# 9V_Converter_Schematic_3_25_2018.net
KiCad netlist of a schematic drawn in Altium Designer
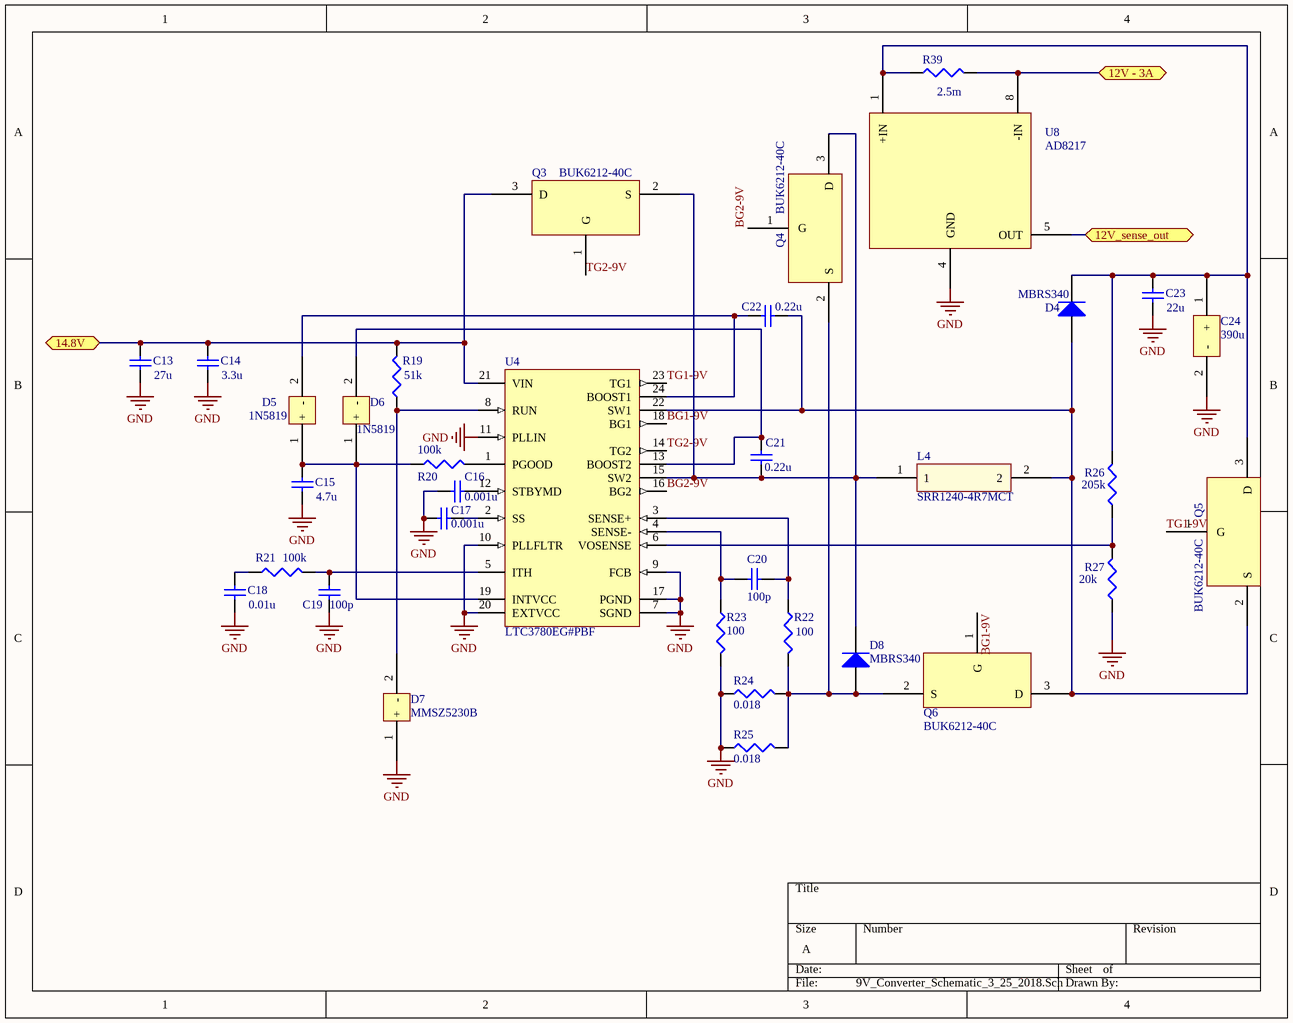
[diagram p0: 9V_Converter_Schematic_3_25_2018.SchDoc]

(export (version "E")
  (design (tool "Eeschema 10.0.6"))
  (components
    (comp (ref "C13")
      (value "27u")
      (footprint "C1206")
      (description "Capacitor (Semiconductor SIM Model)")
      (fields (field (name "Comment") "Cap Semi") (field (name "PUBLISHER") "Altium Limited"))
      (libsource (lib "Miscellaneous Devices") (part "Cap Semi"))
    )
    (comp (ref "C14")
      (value "3.3u")
      (footprint "C1206")
      (description "Capacitor (Semiconductor SIM Model)")
      (fields (field (name "Comment") "Cap Semi") (field (name "PUBLISHER") "Altium Limited"))
      (libsource (lib "Miscellaneous Devices") (part "Cap Semi"))
    )
    (comp (ref "C15")
      (value "4.7u")
      (footprint "C1206")
      (description "Capacitor (Semiconductor SIM Model)")
      (fields (field (name "Comment") "Cap Semi") (field (name "PUBLISHER") "Altium Limited"))
      (libsource (lib "Miscellaneous Devices") (part "Cap Semi"))
    )
    (comp (ref "C16")
      (value "0.001u")
      (footprint "C1206")
      (description "Capacitor (Semiconductor SIM Model)")
      (fields (field (name "Comment") "Cap Semi") (field (name "PUBLISHER") "Altium Limited"))
      (libsource (lib "Miscellaneous Devices") (part "Cap Semi"))
    )
    (comp (ref "C17")
      (value "0.001u")
      (footprint "C1206")
      (description "Capacitor (Semiconductor SIM Model)")
      (fields (field (name "Comment") "Cap Semi") (field (name "PUBLISHER") "Altium Limited"))
      (libsource (lib "Miscellaneous Devices") (part "Cap Semi"))
    )
    (comp (ref "C18")
      (value "0.01u")
      (footprint "C1206")
      (description "Capacitor (Semiconductor SIM Model)")
      (fields (field (name "Comment") "Cap Semi") (field (name "PUBLISHER") "Altium Limited"))
      (libsource (lib "Miscellaneous Devices") (part "Cap Semi"))
    )
    (comp (ref "C19")
      (value "100p")
      (footprint "C1206")
      (description "Capacitor (Semiconductor SIM Model)")
      (fields (field (name "Comment") "Cap Semi") (field (name "PUBLISHER") "Altium Limited"))
      (libsource (lib "Miscellaneous Devices") (part "Cap Semi"))
    )
    (comp (ref "C20")
      (value "100p")
      (footprint "C1206")
      (description "Capacitor (Semiconductor SIM Model)")
      (fields (field (name "Comment") "Cap Semi") (field (name "PUBLISHER") "Altium Limited"))
      (libsource (lib "Miscellaneous Devices") (part "Cap Semi"))
    )
    (comp (ref "C21")
      (value "0.22u")
      (footprint "C1206")
      (description "Capacitor (Semiconductor SIM Model)")
      (fields (field (name "Comment") "Cap Semi") (field (name "PUBLISHER") "Altium Limited"))
      (libsource (lib "Miscellaneous Devices") (part "Cap Semi"))
    )
    (comp (ref "C22")
      (value "0.22u")
      (footprint "C1206")
      (description "Capacitor (Semiconductor SIM Model)")
      (fields (field (name "Comment") "Cap Semi") (field (name "PUBLISHER") "Altium Limited"))
      (libsource (lib "Miscellaneous Devices") (part "Cap Semi"))
    )
    (comp (ref "C23")
      (value "22u")
      (footprint "C1206")
      (description "Capacitor (Semiconductor SIM Model)")
      (fields (field (name "Comment") "Cap Semi") (field (name "PUBLISHER") "Altium Limited"))
      (libsource (lib "Miscellaneous Devices") (part "Cap Semi"))
    )
    (comp (ref "C24") (value "390u") (footprint "Alum_Cap") (libsource (lib "AluminumCap") (part "Alum_Cap")))
    (comp (ref "D4")
      (value "MBRS340")
      (footprint "SMC")
      (description "Default Diode")
      (fields (field (name "PUBLISHER") "Altium Limited"))
      (libsource (lib "Miscellaneous Devices") (part "Diode"))
    )
    (comp (ref "D5")
      (value "1N5819")
      (footprint "SOD-123")
      (libsource (lib "Diode (1N5819)") (part "Component_1"))
    )
    (comp (ref "D6")
      (value "1N5819")
      (footprint "SOD-123")
      (libsource (lib "Diode (1N5819)") (part "Component_1"))
    )
    (comp (ref "D7")
      (value "MMSZ5230B")
      (footprint "SOD-123")
      (libsource (lib "Diode (1N5819)") (part "Component_1"))
    )
    (comp (ref "D8")
      (value "MBRS340")
      (footprint "SMC")
      (description "Default Diode")
      (fields (field (name "PUBLISHER") "Altium Limited"))
      (libsource (lib "Miscellaneous Devices") (part "Diode"))
    )
    (comp (ref "L4")
      (value "SRR1240-4R7MCT")
      (footprint "INDP125125X45N")
      (libsource (lib "SRR1240-4R7MCT") (part "SRR1240-4R7MCT"))
    )
    (comp (ref "Q3")
      (value "BUK6212-40C")
      (footprint "SOT457P1000X238-3N")
      (libsource (lib "") (part "Component_1_2"))
    )
    (comp (ref "Q4")
      (value "BUK6212-40C")
      (footprint "SOT457P1000X238-3N")
      (libsource (lib "") (part "Component_1_1"))
    )
    (comp (ref "Q5")
      (value "BUK6212-40C")
      (footprint "SOT457P1000X238-3N")
      (libsource (lib "") (part "Component_1_1"))
    )
    (comp (ref "Q6")
      (value "BUK6212-40C")
      (footprint "SOT457P1000X238-3N")
      (libsource (lib "BUK6212-40C") (part "Component_1"))
    )
    (comp (ref "R19")
      (value "51k")
      (footprint "J1-0603")
      (description "Resistor")
      (fields (field (name "Comment") "Res3") (field (name "PUBLISHER") "Altium Limited"))
      (libsource (lib "Miscellaneous Devices") (part "Res3"))
    )
    (comp (ref "R20")
      (value "100k")
      (footprint "J1-0603")
      (description "Resistor")
      (fields (field (name "Comment") "Res3") (field (name "PUBLISHER") "Altium Limited"))
      (libsource (lib "Miscellaneous Devices") (part "Res3"))
    )
    (comp (ref "R21")
      (value "100k")
      (footprint "J1-0603")
      (description "Resistor")
      (fields (field (name "Comment") "Res3") (field (name "PUBLISHER") "Altium Limited"))
      (libsource (lib "Miscellaneous Devices") (part "Res3"))
    )
    (comp (ref "R22")
      (value "100")
      (footprint "J1-0603")
      (description "Resistor")
      (fields (field (name "Comment") "Res3") (field (name "PUBLISHER") "Altium Limited"))
      (libsource (lib "Miscellaneous Devices") (part "Res3"))
    )
    (comp (ref "R23")
      (value "100")
      (footprint "J1-0603")
      (description "Resistor")
      (fields (field (name "Comment") "Res3") (field (name "PUBLISHER") "Altium Limited"))
      (libsource (lib "Miscellaneous Devices") (part "Res3"))
    )
    (comp (ref "R24")
      (value "0.018")
      (footprint "J1-0603")
      (description "Resistor")
      (fields (field (name "Comment") "Res3") (field (name "PUBLISHER") "Altium Limited"))
      (libsource (lib "Miscellaneous Devices") (part "Res3"))
    )
    (comp (ref "R25")
      (value "0.018")
      (footprint "J1-0603")
      (description "Resistor")
      (fields (field (name "Comment") "Res3") (field (name "PUBLISHER") "Altium Limited"))
      (libsource (lib "Miscellaneous Devices") (part "Res3"))
    )
    (comp (ref "R26")
      (value "205k")
      (footprint "J1-0603")
      (description "Resistor")
      (fields (field (name "Comment") "Res3") (field (name "PUBLISHER") "Altium Limited"))
      (libsource (lib "Miscellaneous Devices") (part "Res3"))
    )
    (comp (ref "R27")
      (value "20k")
      (footprint "J1-0603")
      (description "Resistor")
      (fields (field (name "Comment") "Res3") (field (name "PUBLISHER") "Altium Limited"))
      (libsource (lib "Miscellaneous Devices") (part "Res3"))
    )
    (comp (ref "R39")
      (value "2.5m")
      (footprint "J1-0603")
      (description "Resistor")
      (fields (field (name "Comment") "Res3") (field (name "PUBLISHER") "Altium Limited"))
      (libsource (lib "Miscellaneous Devices") (part "Res3"))
    )
    (comp (ref "U4")
      (value "LTC3780EG#PBF")
      (footprint "LT-G-24_N")
      (fields (field (name "MANUFACTURER") "Linear Technology"))
      (libsource (lib "Linear Technology Power Management Switching Regulator LTC1174-LTC3901") (part "LTC3780EG#PBF"))
    )
    (comp (ref "U8")
      (value "AD8217")
      (footprint "TSOP65P490X110-8N")
      (description "Current Shunt Moniter")
      (libsource (lib "AD8217") (part "Component_1"))
    )
  )
  (nets
    (net (code "1") (name "/12V - 3A") (class "Default")
      (node (ref "R39") (pin "2") (pinfunction "2_2") (pintype "passive"))
      (node (ref "U8") (pin "8") (pinfunction "-IN_8") (pintype "passive"))
    )
    (net (code "2") (name "/12V_sense_out") (class "Default")
      (node (ref "U8") (pin "5") (pinfunction "OUT_5") (pintype "passive"))
    )
    (net (code "3") (name "/14.8V") (class "Default")
      (node (ref "C13") (pin "2") (pinfunction "2_2") (pintype "passive"))
      (node (ref "C14") (pin "2") (pinfunction "2_2") (pintype "passive"))
      (node (ref "Q3") (pin "3") (pinfunction "D_3") (pintype "passive"))
      (node (ref "R19") (pin "2") (pinfunction "2_2") (pintype "passive"))
      (node (ref "U4") (pin "21") (pinfunction "VIN_21") (pintype "power_in"))
    )
    (net (code "4") (name "/BG1-9V") (class "Default")
      (node (ref "Q6") (pin "1") (pinfunction "G_1") (pintype "passive"))
      (node (ref "U4") (pin "18") (pinfunction "BG1_18") (pintype "output"))
    )
    (net (code "5") (name "/BG2-9V") (class "Default")
      (node (ref "Q4") (pin "1") (pinfunction "G_1") (pintype "passive"))
      (node (ref "U4") (pin "16") (pinfunction "BG2_16") (pintype "output"))
    )
    (net (code "6") (name "/TG1-9V") (class "Default")
      (node (ref "Q5") (pin "1") (pinfunction "G_1") (pintype "passive"))
      (node (ref "U4") (pin "23") (pinfunction "TG1_23") (pintype "output"))
    )
    (net (code "7") (name "/TG2-9V") (class "Default")
      (node (ref "Q3") (pin "1") (pinfunction "G_1") (pintype "passive"))
      (node (ref "U4") (pin "14") (pinfunction "TG2_14") (pintype "output"))
    )
    (net (code "8") (name "GND") (class "Default")
      (node (ref "C13") (pin "1") (pinfunction "1_1") (pintype "passive"))
      (node (ref "C14") (pin "1") (pinfunction "1_1") (pintype "passive"))
      (node (ref "C15") (pin "1") (pinfunction "1_1") (pintype "passive"))
      (node (ref "C16") (pin "1") (pinfunction "1_1") (pintype "passive"))
      (node (ref "C17") (pin "1") (pinfunction "1_1") (pintype "passive"))
      (node (ref "C18") (pin "1") (pinfunction "1_1") (pintype "passive"))
      (node (ref "C19") (pin "1") (pinfunction "1_1") (pintype "passive"))
      (node (ref "C23") (pin "1") (pinfunction "1_1") (pintype "passive"))
      (node (ref "C24") (pin "2") (pinfunction "-_2") (pintype "passive"))
      (node (ref "D7") (pin "1") (pinfunction "+_1") (pintype "passive"))
      (node (ref "R23") (pin "2") (pinfunction "2_2") (pintype "passive"))
      (node (ref "R24") (pin "1") (pinfunction "1_1") (pintype "passive"))
      (node (ref "R25") (pin "1") (pinfunction "1_1") (pintype "passive"))
      (node (ref "R27") (pin "1") (pinfunction "1_1") (pintype "passive"))
      (node (ref "U4") (pin "10") (pinfunction "PLLFLTR_10") (pintype "input"))
      (node (ref "U4") (pin "11") (pinfunction "PLLIN_11") (pintype "input"))
      (node (ref "U4") (pin "17") (pinfunction "PGND_17") (pintype "power_in"))
      (node (ref "U4") (pin "20") (pinfunction "EXTVCC_20") (pintype "power_in"))
      (node (ref "U4") (pin "7") (pinfunction "SGND_7") (pintype "power_in"))
      (node (ref "U4") (pin "9") (pinfunction "FCB_9") (pintype "input"))
      (node (ref "U8") (pin "4") (pinfunction "GND_4") (pintype "passive"))
    )
    (net (code "9") (name "Net-(C18-Pad2)") (class "Default")
      (node (ref "C18") (pin "2") (pinfunction "2_2") (pintype "passive"))
      (node (ref "R21") (pin "1") (pinfunction "1_1") (pintype "passive"))
    )
    (net (code "10") (name "Net-(C24-+)") (class "Default")
      (node (ref "C23") (pin "2") (pinfunction "2_2") (pintype "passive"))
      (node (ref "C24") (pin "1") (pinfunction "+_1") (pintype "passive"))
      (node (ref "D4") (pin "2") (pinfunction "K_2") (pintype "passive"))
      (node (ref "Q5") (pin "3") (pinfunction "D_3") (pintype "passive"))
      (node (ref "R26") (pin "2") (pinfunction "2_2") (pintype "passive"))
      (node (ref "R39") (pin "1") (pinfunction "1_1") (pintype "passive"))
      (node (ref "U8") (pin "1") (pinfunction "+IN_1") (pintype "passive"))
    )
    (net (code "11") (name "Net-(D4-A)") (class "Default")
      (node (ref "C22") (pin "1") (pinfunction "1_1") (pintype "passive"))
      (node (ref "D4") (pin "1") (pinfunction "A_1") (pintype "passive"))
      (node (ref "L4") (pin "2") (pinfunction "2_2") (pintype "passive"))
      (node (ref "Q5") (pin "2") (pinfunction "S_2") (pintype "passive"))
      (node (ref "Q6") (pin "3") (pinfunction "D_3") (pintype "passive"))
      (node (ref "U4") (pin "22") (pinfunction "SW1_22") (pintype "passive"))
    )
    (net (code "12") (name "Net-(D5-+)") (class "Default")
      (node (ref "C15") (pin "2") (pinfunction "2_2") (pintype "passive"))
      (node (ref "D5") (pin "1") (pinfunction "+_1") (pintype "passive"))
      (node (ref "D6") (pin "1") (pinfunction "+_1") (pintype "passive"))
      (node (ref "R20") (pin "1") (pinfunction "1_1") (pintype "passive"))
      (node (ref "U4") (pin "19") (pinfunction "INTVCC_19") (pintype "power_in"))
    )
    (net (code "13") (name "Net-(D5--)") (class "Default")
      (node (ref "C22") (pin "2") (pinfunction "2_2") (pintype "passive"))
      (node (ref "D5") (pin "2") (pinfunction "-_2") (pintype "passive"))
      (node (ref "U4") (pin "24") (pinfunction "BOOST1_24") (pintype "passive"))
    )
    (net (code "14") (name "Net-(D6--)") (class "Default")
      (node (ref "C21") (pin "2") (pinfunction "2_2") (pintype "passive"))
      (node (ref "D6") (pin "2") (pinfunction "-_2") (pintype "passive"))
      (node (ref "U4") (pin "13") (pinfunction "BOOST2_13") (pintype "passive"))
    )
    (net (code "15") (name "Net-(D7--)") (class "Default")
      (node (ref "D7") (pin "2") (pinfunction "-_2") (pintype "passive"))
      (node (ref "R19") (pin "1") (pinfunction "1_1") (pintype "passive"))
      (node (ref "U4") (pin "8") (pinfunction "RUN_8") (pintype "input"))
    )
    (net (code "16") (name "Net-(D8-A)") (class "Default")
      (node (ref "D8") (pin "1") (pinfunction "A_1") (pintype "passive"))
      (node (ref "Q4") (pin "2") (pinfunction "S_2") (pintype "passive"))
      (node (ref "Q6") (pin "2") (pinfunction "S_2") (pintype "passive"))
      (node (ref "R22") (pin "2") (pinfunction "2_2") (pintype "passive"))
      (node (ref "R24") (pin "2") (pinfunction "2_2") (pintype "passive"))
      (node (ref "R25") (pin "2") (pinfunction "2_2") (pintype "passive"))
    )
    (net (code "17") (name "Net-(D8-K)") (class "Default")
      (node (ref "C21") (pin "1") (pinfunction "1_1") (pintype "passive"))
      (node (ref "D8") (pin "2") (pinfunction "K_2") (pintype "passive"))
      (node (ref "L4") (pin "1") (pinfunction "1_1") (pintype "passive"))
      (node (ref "Q3") (pin "2") (pinfunction "S_2") (pintype "passive"))
      (node (ref "Q4") (pin "3") (pinfunction "D_3") (pintype "passive"))
      (node (ref "U4") (pin "15") (pinfunction "SW2_15") (pintype "passive"))
    )
    (net (code "18") (name "Net-(U4-ITH)") (class "Default")
      (node (ref "C19") (pin "2") (pinfunction "2_2") (pintype "passive"))
      (node (ref "R21") (pin "2") (pinfunction "2_2") (pintype "passive"))
      (node (ref "U4") (pin "5") (pinfunction "ITH_5") (pintype "passive"))
    )
    (net (code "19") (name "Net-(U4-PGOOD)") (class "Default")
      (node (ref "R20") (pin "2") (pinfunction "2_2") (pintype "passive"))
      (node (ref "U4") (pin "1") (pinfunction "PGOOD_1") (pintype "open_collector"))
    )
    (net (code "20") (name "Net-(U4-SENSE+)") (class "Default")
      (node (ref "C20") (pin "2") (pinfunction "2_2") (pintype "passive"))
      (node (ref "R22") (pin "1") (pinfunction "1_1") (pintype "passive"))
      (node (ref "U4") (pin "3") (pinfunction "SENSE+_3") (pintype "input"))
    )
    (net (code "21") (name "Net-(U4-SENSE-)") (class "Default")
      (node (ref "C20") (pin "1") (pinfunction "1_1") (pintype "passive"))
      (node (ref "R23") (pin "1") (pinfunction "1_1") (pintype "passive"))
      (node (ref "U4") (pin "4") (pinfunction "SENSE-_4") (pintype "input"))
    )
    (net (code "22") (name "Net-(U4-SS)") (class "Default")
      (node (ref "C17") (pin "2") (pinfunction "2_2") (pintype "passive"))
      (node (ref "U4") (pin "2") (pinfunction "SS_2") (pintype "input"))
    )
    (net (code "23") (name "Net-(U4-STBYMD)") (class "Default")
      (node (ref "C16") (pin "2") (pinfunction "2_2") (pintype "passive"))
      (node (ref "U4") (pin "12") (pinfunction "STBYMD_12") (pintype "input"))
    )
    (net (code "24") (name "Net-(U4-VOSENSE)") (class "Default")
      (node (ref "R26") (pin "1") (pinfunction "1_1") (pintype "passive"))
      (node (ref "R27") (pin "2") (pinfunction "2_2") (pintype "passive"))
      (node (ref "U4") (pin "6") (pinfunction "VOSENSE_6") (pintype "input"))
    )
  )
)
